# Sheet1.net
KiCad netlist of a schematic drawn in Altium Designer
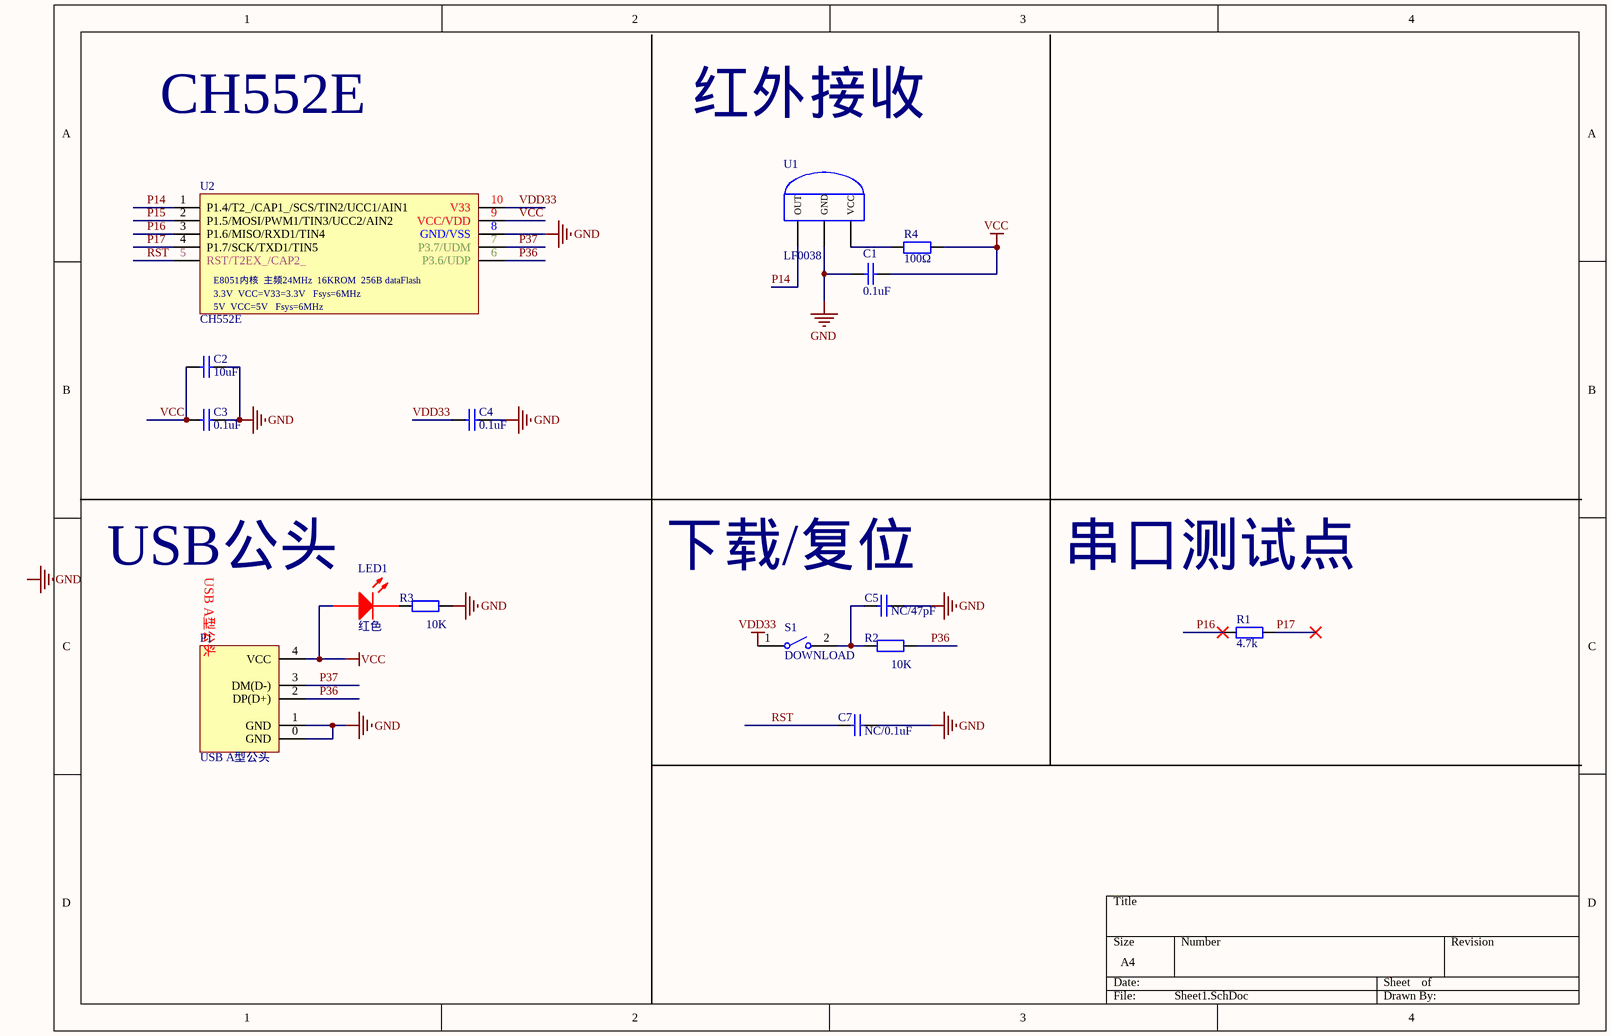
[diagram p0: Sheet1.SchDoc]

(export (version "E")
  (design (tool "Eeschema 10.0.6"))
  (components
    (comp (ref "C1")
      (value "0.1uF")
      (footprint "0603_C")
      (fields (field (name "PUBLISHER") "Altium Limited"))
      (libsource (lib "基础元件库") (part "Cap"))
    )
    (comp (ref "C2")
      (value "10uF")
      (footprint "0603_C")
      (fields (field (name "PUBLISHER") "Altium Limited"))
      (libsource (lib "基础元件库") (part "Cap"))
    )
    (comp (ref "C3")
      (value "0.1uF")
      (footprint "0603_C")
      (fields (field (name "PUBLISHER") "Altium Limited"))
      (libsource (lib "基础元件库") (part "Cap"))
    )
    (comp (ref "C4")
      (value "0.1uF")
      (footprint "0603_C")
      (fields (field (name "PUBLISHER") "Altium Limited"))
      (libsource (lib "基础元件库") (part "Cap"))
    )
    (comp (ref "C5")
      (value "NC/47pF")
      (footprint "0603_C")
      (fields (field (name "PUBLISHER") "Altium Limited"))
      (libsource (lib "基础元件库") (part "Cap"))
    )
    (comp (ref "C7")
      (value "NC/0.1uF")
      (footprint "0603_C")
      (fields (field (name "PUBLISHER") "Altium Limited"))
      (libsource (lib "基础元件库") (part "Cap"))
    )
    (comp (ref "LED1")
      (value "红色")
      (footprint "0603_LED_RED")
      (fields (field (name "PUBLISHER") "Altium Limited"))
      (libsource (lib "基础元件库") (part "LED_RED"))
    )
    (comp (ref "P1") (value "USB A型公头") (footprint "USB_A型公头双面插") (libsource (lib "基础元件库") (part "USB A型公头")))
    (comp (ref "R1")
      (value "4.7k")
      (footprint "0603_R")
      (description "电阻")
      (fields (field (name "PUBLISHER") "Altium Limited"))
      (libsource (lib "PCB_Project") (part "Res"))
    )
    (comp (ref "R2")
      (value "10K")
      (footprint "0603_R")
      (description "电阻")
      (fields (field (name "PUBLISHER") "Altium Limited"))
      (libsource (lib "基础元件库") (part "Res"))
    )
    (comp (ref "R3")
      (value "10K")
      (footprint "0603_R")
      (description "电阻")
      (fields (field (name "PUBLISHER") "Altium Limited"))
      (libsource (lib "基础元件库") (part "Res"))
    )
    (comp (ref "R4")
      (value "100Ω")
      (footprint "0603_R")
      (description "电阻")
      (fields (field (name "PUBLISHER") "Altium Limited"))
      (libsource (lib "基础元件库") (part "Res"))
    )
    (comp (ref "S1")
      (value "DOWNLOAD")
      (footprint "Switch_3*4*2")
      (fields (field (name "PUBLISHER") "Altium Limited"))
      (libsource (lib "基础元件库") (part "Switch"))
    )
    (comp (ref "U1") (value "LF0038") (footprint "4mm贴片红外接收头") (libsource (lib "基础元件库") (part "LF0038")))
    (comp (ref "U2")
      (value "CH552E")
      (footprint "MSOP-10")
      (description "10-bit")
      (libsource (lib "MCU") (part "CH552E MSOP10"))
    )
  )
  (nets
    (net (code "1") (name "/P14") (class "Default")
      (node (ref "U1") (pin "1") (pinfunction "OUT_1") (pintype "passive"))
      (node (ref "U2") (pin "1") (pinfunction "P1.4/T2_/CAP1_/SCS/TIN2/UCC1/AIN1_1") (pintype "passive"))
    )
    (net (code "2") (name "/P15") (class "Default")
      (node (ref "U2") (pin "2") (pinfunction "P1.5/MOSI/PWM1/TIN3/UCC2/AIN2_2") (pintype "passive"))
    )
    (net (code "3") (name "/P16") (class "Default")
      (node (ref "R1") (pin "1") (pintype "passive"))
      (node (ref "U2") (pin "3") (pinfunction "P1.6/MISO/RXD1/TIN4_3") (pintype "passive"))
    )
    (net (code "4") (name "/P17") (class "Default")
      (node (ref "R1") (pin "2") (pintype "passive"))
      (node (ref "U2") (pin "4") (pinfunction "P1.7/SCK/TXD1/TIN5_4") (pintype "passive"))
    )
    (net (code "5") (name "/P36") (class "Default")
      (node (ref "P1") (pin "2") (pinfunction "DP(D+)_2") (pintype "passive"))
      (node (ref "R2") (pin "2") (pintype "passive"))
      (node (ref "U2") (pin "6") (pinfunction "P3.6/UDP_6") (pintype "passive"))
    )
    (net (code "6") (name "/P37") (class "Default")
      (node (ref "P1") (pin "3") (pinfunction "DM(D-)_3") (pintype "passive"))
      (node (ref "U2") (pin "7") (pinfunction "P3.7/UDM_7") (pintype "passive"))
    )
    (net (code "7") (name "/RST") (class "Default")
      (node (ref "C7") (pin "1") (pintype "power_in"))
      (node (ref "U2") (pin "5") (pinfunction "RST/T2EX_/CAP2__5") (pintype "passive"))
    )
    (net (code "8") (name "GND") (class "Default")
      (node (ref "C1") (pin "2") (pintype "power_in"))
      (node (ref "C2") (pin "2") (pintype "power_in"))
      (node (ref "C3") (pin "2") (pintype "power_in"))
      (node (ref "C4") (pin "2") (pintype "power_in"))
      (node (ref "C5") (pin "2") (pintype "power_in"))
      (node (ref "C7") (pin "2") (pintype "power_in"))
      (node (ref "P1") (pin "0") (pinfunction "GND_0") (pintype "passive"))
      (node (ref "P1") (pin "1") (pinfunction "GND_1") (pintype "passive"))
      (node (ref "R3") (pin "2") (pintype "passive"))
      (node (ref "U1") (pin "2") (pinfunction "GND_2") (pintype "passive"))
      (node (ref "U2") (pin "8") (pinfunction "GND/VSS_8") (pintype "passive"))
    )
    (net (code "9") (name "Net-(C5-Pad1)") (class "Default")
      (node (ref "C5") (pin "1") (pintype "power_in"))
      (node (ref "R2") (pin "1") (pintype "passive"))
      (node (ref "S1") (pin "2") (pintype "passive"))
    )
    (net (code "10") (name "Net-(LED1-Pad2)") (class "Default")
      (node (ref "LED1") (pin "2") (pintype "passive"))
      (node (ref "R3") (pin "1") (pintype "passive"))
    )
    (net (code "11") (name "Net-(U1-VCC)") (class "Default")
      (node (ref "R4") (pin "1") (pintype "passive"))
      (node (ref "U1") (pin "3") (pinfunction "VCC_3") (pintype "passive"))
    )
    (net (code "12") (name "VCC") (class "Default")
      (node (ref "C1") (pin "1") (pintype "power_in"))
      (node (ref "C2") (pin "1") (pintype "power_in"))
      (node (ref "C3") (pin "1") (pintype "power_in"))
      (node (ref "LED1") (pin "1") (pintype "passive"))
      (node (ref "P1") (pin "4") (pinfunction "VCC_4") (pintype "passive"))
      (node (ref "R4") (pin "2") (pintype "passive"))
      (node (ref "U2") (pin "9") (pinfunction "VCC/VDD_9") (pintype "passive"))
    )
    (net (code "13") (name "VDD33") (class "Default")
      (node (ref "C4") (pin "1") (pintype "power_in"))
      (node (ref "S1") (pin "1") (pintype "passive"))
      (node (ref "U2") (pin "10") (pinfunction "V33_10") (pintype "passive"))
    )
  )
)
